# MGNGSQ4_Loopback.net
KiCad netlist of a schematic drawn in Altium Designer
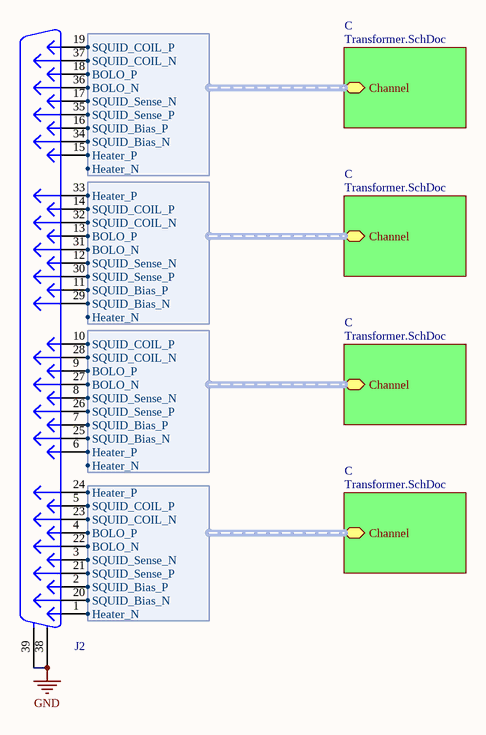
[diagram p0: MGNGSQ4_Loopback.SchDoc]

(export (version "E")
  (design (tool "Eeschema 10.0.6"))
  (components
    (comp (ref "J2")
      (value "DB37M")
      (footprint "DSUB37-M")
      (libsource (lib "MGNGSQ4_Dongles") (part "DB37M"))
    )
  )
  (nets
    (net (code "3") (name "GND") (class "Default")
      (node (ref "J2") (pin "38") (pinfunction "MH1_38") (pintype "passive"))
      (node (ref "J2") (pin "39") (pinfunction "MH2_39") (pintype "passive"))
    )
    (net (code "4") (name "unconnected-(J2-Pad1)") (class "Default")
      (node (ref "J2") (pin "1") (pinfunction "1_1") (pintype "passive"))
    )
    (net (code "5") (name "unconnected-(J2-Pad2)") (class "Default")
      (node (ref "J2") (pin "2") (pinfunction "2_2") (pintype "passive"))
    )
    (net (code "6") (name "unconnected-(J2-Pad3)") (class "Default")
      (node (ref "J2") (pin "3") (pinfunction "3_3") (pintype "passive"))
    )
    (net (code "7") (name "unconnected-(J2-Pad4)") (class "Default")
      (node (ref "J2") (pin "4") (pinfunction "4_4") (pintype "passive"))
    )
    (net (code "8") (name "unconnected-(J2-Pad5)") (class "Default")
      (node (ref "J2") (pin "5") (pinfunction "5_5") (pintype "passive"))
    )
    (net (code "9") (name "unconnected-(J2-Pad6)") (class "Default")
      (node (ref "J2") (pin "6") (pinfunction "6_6") (pintype "passive"))
    )
    (net (code "10") (name "unconnected-(J2-Pad7)") (class "Default")
      (node (ref "J2") (pin "7") (pinfunction "7_7") (pintype "passive"))
    )
    (net (code "11") (name "unconnected-(J2-Pad8)") (class "Default")
      (node (ref "J2") (pin "8") (pinfunction "8_8") (pintype "passive"))
    )
    (net (code "12") (name "unconnected-(J2-Pad9)") (class "Default")
      (node (ref "J2") (pin "9") (pinfunction "9_9") (pintype "passive"))
    )
    (net (code "13") (name "unconnected-(J2-Pad10)") (class "Default")
      (node (ref "J2") (pin "10") (pinfunction "10_10") (pintype "passive"))
    )
    (net (code "14") (name "unconnected-(J2-Pad11)") (class "Default")
      (node (ref "J2") (pin "11") (pinfunction "11_11") (pintype "passive"))
    )
    (net (code "15") (name "unconnected-(J2-Pad12)") (class "Default")
      (node (ref "J2") (pin "12") (pinfunction "12_12") (pintype "passive"))
    )
    (net (code "16") (name "unconnected-(J2-Pad13)") (class "Default")
      (node (ref "J2") (pin "13") (pinfunction "13_13") (pintype "passive"))
    )
    (net (code "17") (name "unconnected-(J2-Pad14)") (class "Default")
      (node (ref "J2") (pin "14") (pinfunction "14_14") (pintype "passive"))
    )
    (net (code "18") (name "unconnected-(J2-Pad15)") (class "Default")
      (node (ref "J2") (pin "15") (pinfunction "15_15") (pintype "passive"))
    )
    (net (code "19") (name "unconnected-(J2-Pad16)") (class "Default")
      (node (ref "J2") (pin "16") (pinfunction "16_16") (pintype "passive"))
    )
    (net (code "20") (name "unconnected-(J2-Pad17)") (class "Default")
      (node (ref "J2") (pin "17") (pinfunction "17_17") (pintype "passive"))
    )
    (net (code "21") (name "unconnected-(J2-Pad18)") (class "Default")
      (node (ref "J2") (pin "18") (pinfunction "18_18") (pintype "passive"))
    )
    (net (code "22") (name "unconnected-(J2-Pad19)") (class "Default")
      (node (ref "J2") (pin "19") (pinfunction "19_19") (pintype "passive"))
    )
    (net (code "23") (name "unconnected-(J2-Pad20)") (class "Default")
      (node (ref "J2") (pin "20") (pinfunction "20_20") (pintype "passive"))
    )
    (net (code "24") (name "unconnected-(J2-Pad21)") (class "Default")
      (node (ref "J2") (pin "21") (pinfunction "21_21") (pintype "passive"))
    )
    (net (code "25") (name "unconnected-(J2-Pad22)") (class "Default")
      (node (ref "J2") (pin "22") (pinfunction "22_22") (pintype "passive"))
    )
    (net (code "26") (name "unconnected-(J2-Pad23)") (class "Default")
      (node (ref "J2") (pin "23") (pinfunction "23_23") (pintype "passive"))
    )
    (net (code "27") (name "unconnected-(J2-Pad24)") (class "Default")
      (node (ref "J2") (pin "24") (pinfunction "24_24") (pintype "passive"))
    )
    (net (code "28") (name "unconnected-(J2-Pad25)") (class "Default")
      (node (ref "J2") (pin "25") (pinfunction "25_25") (pintype "passive"))
    )
    (net (code "29") (name "unconnected-(J2-Pad26)") (class "Default")
      (node (ref "J2") (pin "26") (pinfunction "26_26") (pintype "passive"))
    )
    (net (code "30") (name "unconnected-(J2-Pad27)") (class "Default")
      (node (ref "J2") (pin "27") (pinfunction "27_27") (pintype "passive"))
    )
    (net (code "31") (name "unconnected-(J2-Pad28)") (class "Default")
      (node (ref "J2") (pin "28") (pinfunction "28_28") (pintype "passive"))
    )
    (net (code "32") (name "unconnected-(J2-Pad29)") (class "Default")
      (node (ref "J2") (pin "29") (pinfunction "29_29") (pintype "passive"))
    )
    (net (code "33") (name "unconnected-(J2-Pad30)") (class "Default")
      (node (ref "J2") (pin "30") (pinfunction "30_30") (pintype "passive"))
    )
    (net (code "34") (name "unconnected-(J2-Pad31)") (class "Default")
      (node (ref "J2") (pin "31") (pinfunction "31_31") (pintype "passive"))
    )
    (net (code "35") (name "unconnected-(J2-Pad32)") (class "Default")
      (node (ref "J2") (pin "32") (pinfunction "32_32") (pintype "passive"))
    )
    (net (code "36") (name "unconnected-(J2-Pad33)") (class "Default")
      (node (ref "J2") (pin "33") (pinfunction "33_33") (pintype "passive"))
    )
    (net (code "37") (name "unconnected-(J2-Pad34)") (class "Default")
      (node (ref "J2") (pin "34") (pinfunction "34_34") (pintype "passive"))
    )
    (net (code "38") (name "unconnected-(J2-Pad35)") (class "Default")
      (node (ref "J2") (pin "35") (pinfunction "35_35") (pintype "passive"))
    )
    (net (code "39") (name "unconnected-(J2-Pad36)") (class "Default")
      (node (ref "J2") (pin "36") (pinfunction "36_36") (pintype "passive"))
    )
    (net (code "40") (name "unconnected-(J2-Pad37)") (class "Default")
      (node (ref "J2") (pin "37") (pinfunction "37_37") (pintype "passive"))
    )
  )
)
